# Caravan_Tracker.net
KiCad netlist of a schematic drawn in EAGLE
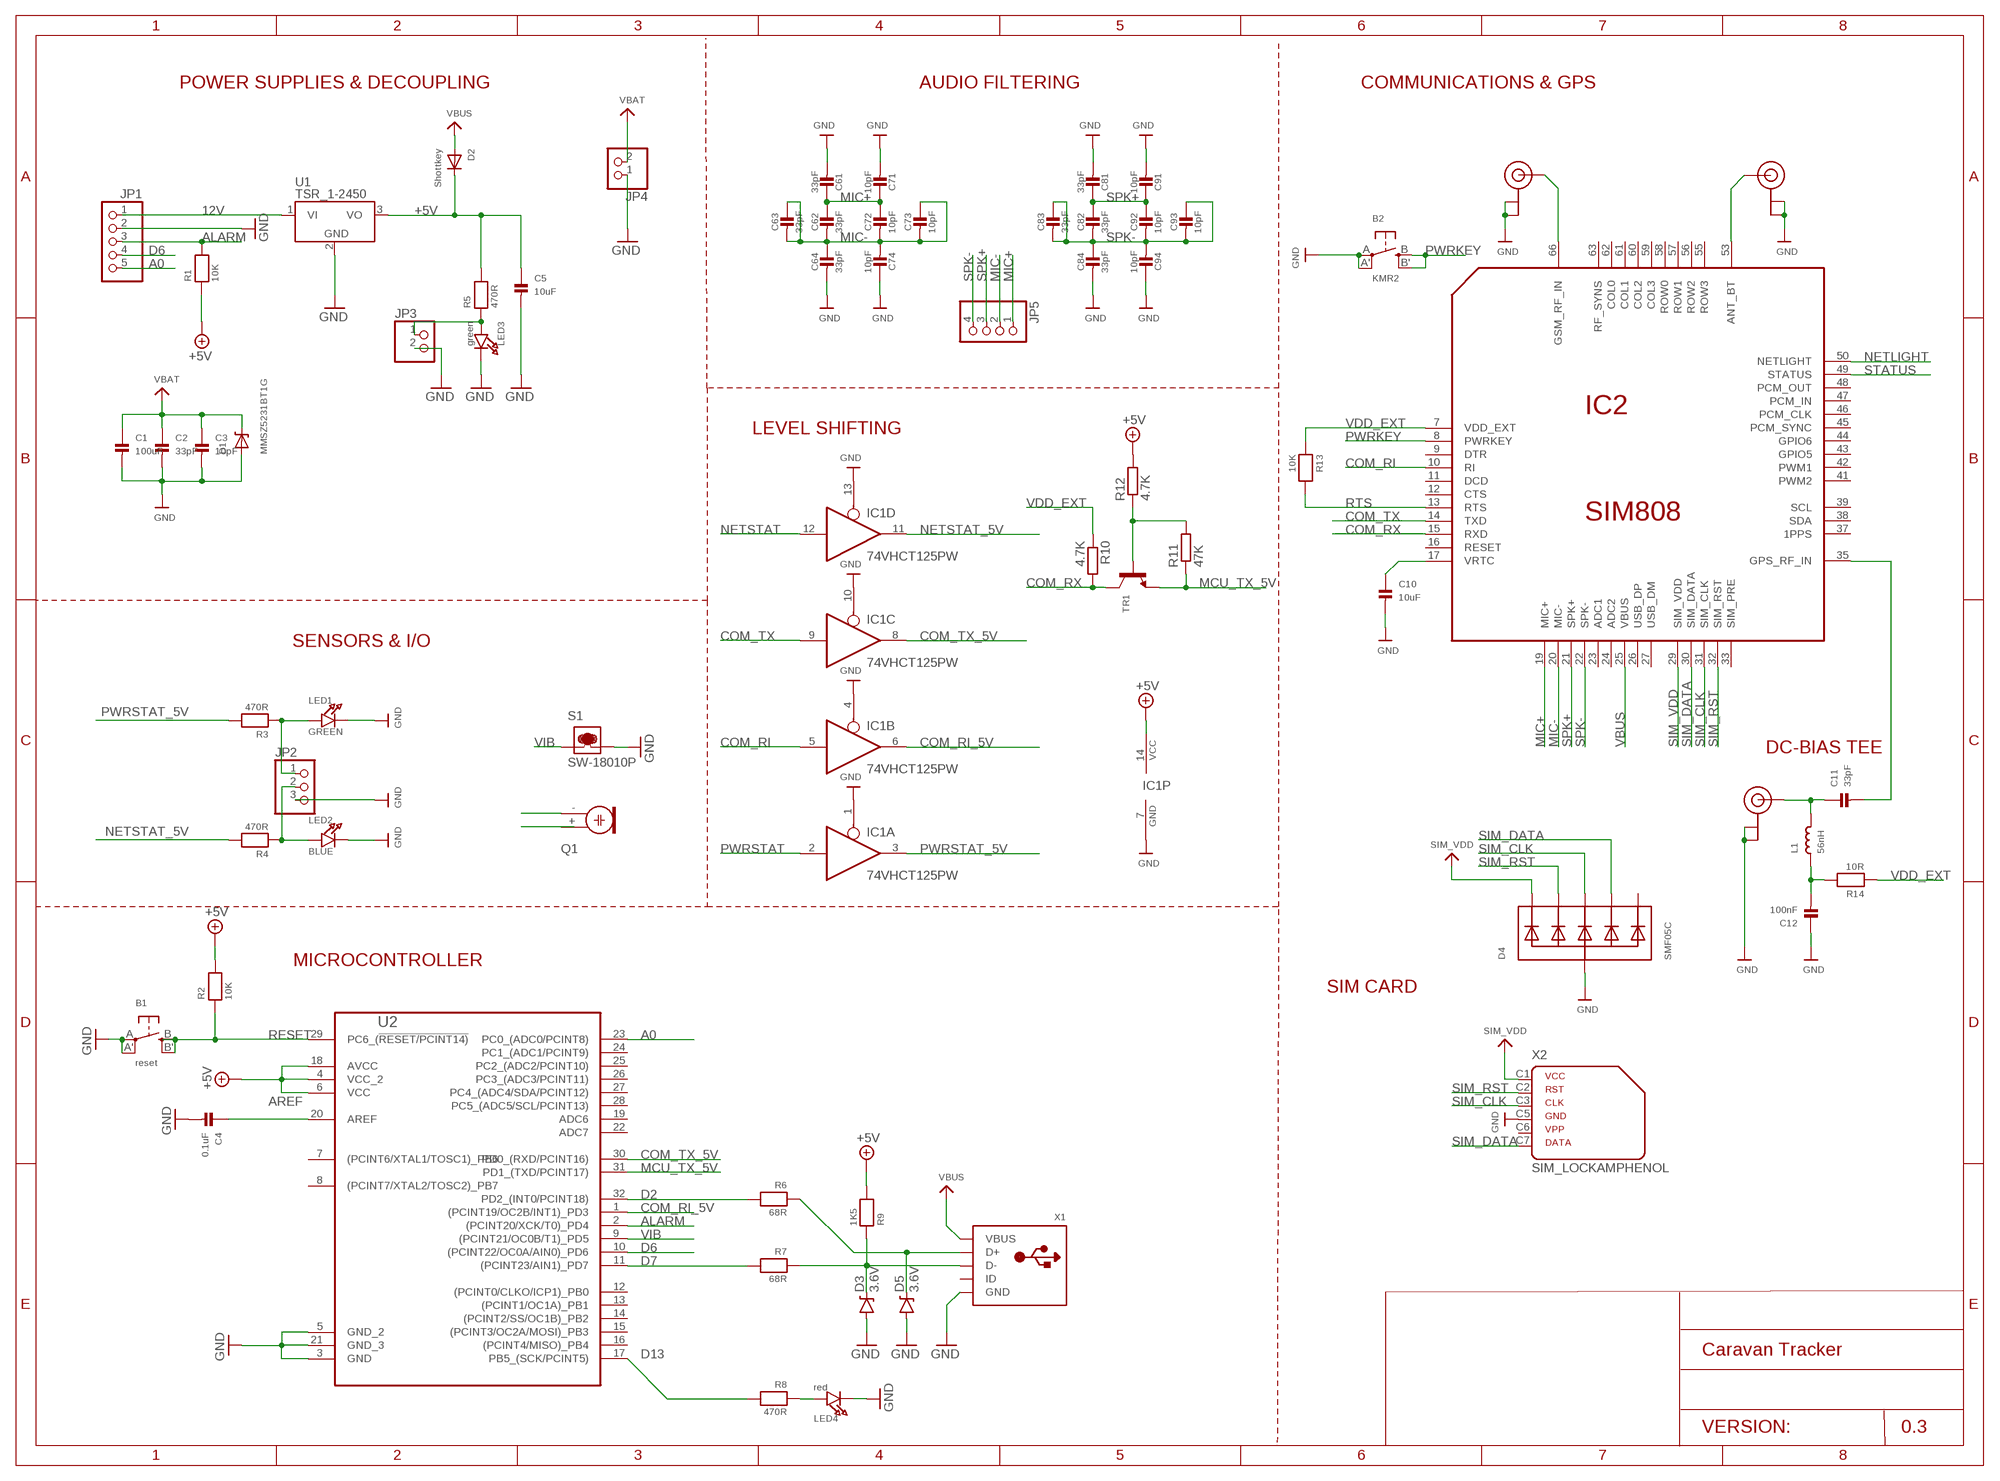
[diagram p0: schematic, sheet 1]

(export (version "E")
  (design (tool "Eeschema 10.0.6"))
  (components
    (comp (ref "B1")
      (value "reset")
      (footprint "eagle-import:BTN_KMR2_4.6X2.8")
      (libsource (lib "eagle-import") (part "SWITCH_TACT_SMT4.6X2.8"))
    )
    (comp (ref "B2")
      (value "KMR2")
      (footprint "eagle-import:BTN_KMR2_4.6X2.8")
      (libsource (lib "eagle-import") (part "SWITCH_TACT_SMT4.6X2.8"))
    )
    (comp (ref "C1")
      (value "100uF")
      (footprint "eagle-import:1206")
      (libsource (lib "eagle-import") (part "CAP_CERAMIC1206"))
    )
    (comp (ref "C2")
      (value "33pF")
      (footprint "eagle-import:0805")
      (libsource (lib "eagle-import") (part "CAP_CERAMIC0805"))
    )
    (comp (ref "C3")
      (value "10pF")
      (footprint "eagle-import:0805")
      (libsource (lib "eagle-import") (part "CAP_CERAMIC0805"))
    )
    (comp (ref "C4")
      (value "0.1uF")
      (footprint "eagle-import:0603")
      (libsource (lib "eagle-import") (part "CAP_CERAMIC0603"))
    )
    (comp (ref "C5")
      (value "10uF")
      (footprint "eagle-import:0603")
      (libsource (lib "eagle-import") (part "CAP_CERAMIC0603"))
    )
    (comp (ref "C6")
      (value "33pF")
      (footprint "eagle-import:RESPACK_4X0603")
      (libsource (lib "eagle-import") (part "CAP_4PACK1206"))
    )
    (comp (ref "C7")
      (value "10pF")
      (footprint "eagle-import:RESPACK_4X0603")
      (libsource (lib "eagle-import") (part "CAP_4PACK1206"))
    )
    (comp (ref "C8")
      (value "33pF")
      (footprint "eagle-import:RESPACK_4X0603")
      (libsource (lib "eagle-import") (part "CAP_4PACK1206"))
    )
    (comp (ref "C9")
      (value "10pF")
      (footprint "eagle-import:RESPACK_4X0603")
      (libsource (lib "eagle-import") (part "CAP_4PACK1206"))
    )
    (comp (ref "C10")
      (value "10uF")
      (footprint "eagle-import:0805")
      (libsource (lib "eagle-import") (part "CAP_CERAMIC0805"))
    )
    (comp (ref "C11")
      (value "33pF")
      (footprint "eagle-import:0805")
      (libsource (lib "eagle-import") (part "CAP_CERAMIC0805"))
    )
    (comp (ref "C12")
      (value "100nF")
      (footprint "eagle-import:0805")
      (libsource (lib "eagle-import") (part "CAP_CERAMIC0805"))
    )
    (comp (ref "D1")
      (value "MMSZ5231BT1G")
      (footprint "eagle-import:SOD-123")
      (libsource (lib "eagle-import") (part "DIODE-ZENERSOD123"))
    )
    (comp (ref "D2")
      (value "Shottkey")
      (footprint "eagle-import:SOD-123")
      (libsource (lib "eagle-import") (part "DIODESOD-123"))
    )
    (comp (ref "D3")
      (value "3.6V")
      (footprint "eagle-import:SOD-323")
      (libsource (lib "eagle-import") (part "DIODE-ZENER3.3V"))
    )
    (comp (ref "D4")
      (value "SMF05C")
      (footprint "eagle-import:SOT363")
      (libsource (lib "eagle-import") (part "TVSARRAY_5LANE"))
    )
    (comp (ref "D5")
      (value "3.6V")
      (footprint "eagle-import:SOD-323")
      (libsource (lib "eagle-import") (part "DIODE-ZENER3.3V"))
    )
    (comp (ref "IC1")
      (value "74VHCT125PW")
      (footprint "eagle-import:TSSOP14")
      (libsource (lib "eagle-import") (part "74125PWABT"))
    )
    (comp (ref "IC2")
      (value "SIM808")
      (footprint "eagle-import:SIM808")
      (libsource (lib "eagle-import") (part "SIM808"))
    )
    (comp (ref "JP1")
      (value "HEADER-1X5ROUND")
      (footprint "eagle-import:1X05_ROUND")
      (libsource (lib "eagle-import") (part "HEADER-1X5ROUND"))
    )
    (comp (ref "JP2")
      (value "HEADER-1X3ROUND")
      (footprint "eagle-import:1X03_ROUND")
      (libsource (lib "eagle-import") (part "HEADER-1X3ROUND"))
    )
    (comp (ref "JP3")
      (value "HEADER-1X2ROUND")
      (footprint "eagle-import:1X02_ROUND")
      (libsource (lib "eagle-import") (part "HEADER-1X2ROUND"))
    )
    (comp (ref "JP4")
      (value "JST_2PIN")
      (footprint "eagle-import:JSTPH2")
      (libsource (lib "eagle-import") (part "JST_2PIN"))
    )
    (comp (ref "JP5")
      (value "HEADER-1X4ROUND")
      (footprint "eagle-import:1X04_ROUND")
      (libsource (lib "eagle-import") (part "HEADER-1X4ROUND"))
    )
    (comp (ref "L1")
      (value "56nH")
      (footprint "eagle-import:_0805")
      (libsource (lib "eagle-import") (part "INDUCTOR_0805"))
    )
    (comp (ref "LED1")
      (value "GREEN")
      (footprint "eagle-import:CHIPLED_0805_NOOUTLINE")
      (libsource (lib "eagle-import") (part "LED0805_NOOUTLINE"))
    )
    (comp (ref "LED2")
      (value "BLUE")
      (footprint "eagle-import:CHIPLED_0805_NOOUTLINE")
      (libsource (lib "eagle-import") (part "LED0805_NOOUTLINE"))
    )
    (comp (ref "LED3")
      (value "green")
      (footprint "eagle-import:CHIPLED_0805_NOOUTLINE")
      (libsource (lib "eagle-import") (part "LED0805_NOOUTLINE"))
    )
    (comp (ref "LED4")
      (value "red")
      (footprint "eagle-import:CHIPLED_0805_NOOUTLINE")
      (libsource (lib "eagle-import") (part "LED0805_NOOUTLINE"))
    )
    (comp (ref "Q1")
      (value "ELECTRET")
      (footprint "eagle-import:9.7ELECTRET")
      (libsource (lib "eagle-import") (part "ELECTRET"))
    )
    (comp (ref "R1")
      (value "10K")
      (footprint "eagle-import:0603")
      (libsource (lib "eagle-import") (part "RESISTOR0603"))
    )
    (comp (ref "R2")
      (value "10K")
      (footprint "eagle-import:0603")
      (libsource (lib "eagle-import") (part "RESISTOR0603"))
    )
    (comp (ref "R3")
      (value "470R")
      (footprint "eagle-import:0603")
      (libsource (lib "eagle-import") (part "RESISTOR0603"))
    )
    (comp (ref "R4")
      (value "470R")
      (footprint "eagle-import:0603")
      (libsource (lib "eagle-import") (part "RESISTOR0603"))
    )
    (comp (ref "R5")
      (value "470R")
      (footprint "eagle-import:0603")
      (libsource (lib "eagle-import") (part "RESISTOR0603"))
    )
    (comp (ref "R6")
      (value "68R")
      (footprint "eagle-import:0603")
      (libsource (lib "eagle-import") (part "RESISTOR0603"))
    )
    (comp (ref "R7")
      (value "68R")
      (footprint "eagle-import:0603")
      (libsource (lib "eagle-import") (part "RESISTOR0603"))
    )
    (comp (ref "R8")
      (value "470R")
      (footprint "eagle-import:0603")
      (libsource (lib "eagle-import") (part "RESISTOR0603"))
    )
    (comp (ref "R9")
      (value "1K5")
      (footprint "eagle-import:0603")
      (libsource (lib "eagle-import") (part "RESISTOR0603"))
    )
    (comp (ref "R10")
      (value "4.7K")
      (footprint "eagle-import:R0603")
      (libsource (lib "eagle-import") (part "R-EU_R0603"))
    )
    (comp (ref "R11")
      (value "47K")
      (footprint "eagle-import:R0603")
      (libsource (lib "eagle-import") (part "R-EU_R0603"))
    )
    (comp (ref "R12")
      (value "4.7K")
      (footprint "eagle-import:R0603")
      (libsource (lib "eagle-import") (part "R-EU_R0603"))
    )
    (comp (ref "R13")
      (value "10K")
      (footprint "eagle-import:0603")
      (libsource (lib "eagle-import") (part "RESISTOR0603"))
    )
    (comp (ref "R14")
      (value "10R")
      (footprint "eagle-import:_0805")
      (libsource (lib "eagle-import") (part "RESISTOR_0805"))
    )
    (comp (ref "S1")
      (value "SW-18010P")
      (footprint "eagle-import:SW-18010P")
      (libsource (lib "eagle-import") (part "SW-18010P"))
    )
    (comp (ref "TR1")
      (value "TRANSISTOR_NPN")
      (footprint "eagle-import:SOT23-R")
      (libsource (lib "eagle-import") (part "TRANSISTOR_NPN"))
    )
    (comp (ref "U$1")
      (value "U.FL (GPS)")
      (footprint "eagle-import:U.FL")
      (libsource (lib "eagle-import") (part "U.FL"))
    )
    (comp (ref "U$2")
      (value "U.FL")
      (footprint "eagle-import:U.FL")
      (libsource (lib "eagle-import") (part "U.FL"))
    )
    (comp (ref "U$3")
      (value "U.FL")
      (footprint "eagle-import:U.FL")
      (libsource (lib "eagle-import") (part "U.FL"))
    )
    (comp (ref "U1")
      (value "TSR_1-2450")
      (footprint "eagle-import:TSR-1")
      (libsource (lib "eagle-import") (part "TSR_1-2450"))
    )
    (comp (ref "U2")
      (value "ATMEGA328-AU")
      (footprint "eagle-import:QFP80P900X900X120-32N")
      (libsource (lib "eagle-import") (part "ATMEGA328-AU"))
    )
    (comp (ref "X1")
      (value "USBMICRO_20329")
      (footprint "eagle-import:4UCONN_20329")
      (libsource (lib "eagle-import") (part "USBMICRO_20329"))
    )
    (comp (ref "X2")
      (value "SIM_LOCKAMPHENOL")
      (footprint "eagle-import:C707_10M006_512_2")
      (libsource (lib "eagle-import") (part "SIM_LOCKAMPHENOL"))
    )
  )
  (nets
    (net (code "1") (name "+5V") (class "Default")
      (node (ref "C5") (pin "1") (pinfunction "P$1_1") (pintype "passive"))
      (node (ref "D2") (pin "C") (pinfunction "C_C") (pintype "passive"))
      (node (ref "IC1") (pin "14") (pinfunction "VCC_14") (pintype "power_in"))
      (node (ref "R1") (pin "1") (pinfunction "1_1") (pintype "passive"))
      (node (ref "R12") (pin "2") (pinfunction "2_2") (pintype "passive"))
      (node (ref "R2") (pin "2") (pinfunction "2_2") (pintype "passive"))
      (node (ref "R5") (pin "2") (pinfunction "2_2") (pintype "passive"))
      (node (ref "R9") (pin "2") (pinfunction "2_2") (pintype "passive"))
      (node (ref "U1") (pin "3") (pinfunction "VO_3") (pintype "power_in"))
      (node (ref "U2") (pin "18") (pinfunction "AVCC_18") (pintype "power_in"))
      (node (ref "U2") (pin "4") (pinfunction "VCC_2_4") (pintype "power_in"))
      (node (ref "U2") (pin "6") (pinfunction "VCC_6") (pintype "power_in"))
    )
    (net (code "2") (name "/12V") (class "Default")
      (node (ref "JP1") (pin "1") (pinfunction "1_1") (pintype "passive"))
      (node (ref "U1") (pin "1") (pinfunction "VI_1") (pintype "power_in"))
    )
    (net (code "3") (name "/A0") (class "Default")
      (node (ref "JP1") (pin "5") (pinfunction "5_5") (pintype "passive"))
      (node (ref "U2") (pin "23") (pinfunction "PC0_(ADC0/PCINT8)_23") (pintype "bidirectional"))
    )
    (net (code "4") (name "/ALARM") (class "Default")
      (node (ref "JP1") (pin "3") (pinfunction "3_3") (pintype "passive"))
      (node (ref "R1") (pin "2") (pinfunction "2_2") (pintype "passive"))
      (node (ref "U2") (pin "2") (pinfunction "(PCINT20/XCK/T0)_PD4_2") (pintype "bidirectional"))
    )
    (net (code "5") (name "/AREF") (class "Default")
      (node (ref "C4") (pin "1") (pinfunction "P$1_1") (pintype "passive"))
      (node (ref "U2") (pin "20") (pinfunction "AREF_20") (pintype "passive"))
    )
    (net (code "6") (name "/COM_RI") (class "Default")
      (node (ref "IC1") (pin "5") (pinfunction "I_5") (pintype "input"))
      (node (ref "IC2") (pin "10") (pinfunction "RI_10") (pintype "bidirectional"))
    )
    (net (code "7") (name "/COM_RI_5V") (class "Default")
      (node (ref "IC1") (pin "6") (pinfunction "O_6") (pintype "tri_state"))
      (node (ref "U2") (pin "1") (pinfunction "(PCINT19/OC2B/INT1)_PD3_1") (pintype "bidirectional"))
    )
    (net (code "8") (name "/COM_RX") (class "Default")
      (node (ref "IC2") (pin "15") (pinfunction "RXD_15") (pintype "bidirectional"))
      (node (ref "R10") (pin "2") (pinfunction "2_2") (pintype "passive"))
      (node (ref "TR1") (pin "3") (pinfunction "C_3") (pintype "passive"))
    )
    (net (code "9") (name "/COM_TX") (class "Default")
      (node (ref "IC1") (pin "9") (pinfunction "I_9") (pintype "input"))
      (node (ref "IC2") (pin "14") (pinfunction "TXD_14") (pintype "bidirectional"))
    )
    (net (code "10") (name "/COM_TX_5V") (class "Default")
      (node (ref "IC1") (pin "8") (pinfunction "O_8") (pintype "tri_state"))
      (node (ref "U2") (pin "30") (pinfunction "PD0_(RXD/PCINT16)_30") (pintype "bidirectional"))
    )
    (net (code "11") (name "/D2") (class "Default")
      (node (ref "R6") (pin "2") (pinfunction "2_2") (pintype "passive"))
      (node (ref "U2") (pin "32") (pinfunction "PD2_(INT0/PCINT18)_32") (pintype "bidirectional"))
    )
    (net (code "12") (name "/D6") (class "Default")
      (node (ref "JP1") (pin "4") (pinfunction "4_4") (pintype "passive"))
      (node (ref "U2") (pin "10") (pinfunction "(PCINT22/OC0A/AIN0)_PD6_10") (pintype "bidirectional"))
    )
    (net (code "13") (name "/D7") (class "Default")
      (node (ref "R7") (pin "2") (pinfunction "2_2") (pintype "passive"))
      (node (ref "U2") (pin "11") (pinfunction "(PCINT23/AIN1)_PD7_11") (pintype "bidirectional"))
    )
    (net (code "14") (name "/D13") (class "Default")
      (node (ref "R8") (pin "2") (pinfunction "2_2") (pintype "passive"))
      (node (ref "U2") (pin "17") (pinfunction "PB5_(SCK/PCINT5)_17") (pintype "bidirectional"))
    )
    (net (code "15") (name "/MCU_TX_5V") (class "Default")
      (node (ref "R11") (pin "1") (pinfunction "1_1") (pintype "passive"))
      (node (ref "TR1") (pin "2") (pinfunction "E_2") (pintype "passive"))
      (node (ref "U2") (pin "31") (pinfunction "PD1_(TXD/PCINT17)_31") (pintype "bidirectional"))
    )
    (net (code "16") (name "/MIC+") (class "Default")
      (node (ref "C6") (pin "1") (pinfunction "1_1") (pintype "passive"))
      (node (ref "C6") (pin "2") (pinfunction "1_2") (pintype "passive"))
      (node (ref "C7") (pin "1") (pinfunction "1_1") (pintype "passive"))
      (node (ref "C7") (pin "2") (pinfunction "1_2") (pintype "passive"))
      (node (ref "IC2") (pin "19") (pinfunction "MIC+_19") (pintype "bidirectional"))
      (node (ref "JP5") (pin "1") (pinfunction "1_1") (pintype "passive"))
    )
    (net (code "17") (name "/MIC-") (class "Default")
      (node (ref "C6") (pin "3") (pinfunction "1_3") (pintype "passive"))
      (node (ref "C6") (pin "4") (pinfunction "1_4") (pintype "passive"))
      (node (ref "C6") (pin "6") (pinfunction "2_6") (pintype "passive"))
      (node (ref "C6") (pin "7") (pinfunction "2_7") (pintype "passive"))
      (node (ref "C7") (pin "3") (pinfunction "1_3") (pintype "passive"))
      (node (ref "C7") (pin "5") (pinfunction "2_5") (pintype "passive"))
      (node (ref "C7") (pin "6") (pinfunction "2_6") (pintype "passive"))
      (node (ref "C7") (pin "7") (pinfunction "2_7") (pintype "passive"))
      (node (ref "IC2") (pin "20") (pinfunction "MIC-_20") (pintype "bidirectional"))
      (node (ref "JP5") (pin "2") (pinfunction "2_2") (pintype "passive"))
      (node (ref "Q1") (pin "-") (pinfunction "1_-") (pintype "passive"))
    )
    (net (code "18") (name "/NETLIGHT") (class "Default")
      (node (ref "IC2") (pin "50") (pinfunction "NETLIGHT_50") (pintype "bidirectional"))
    )
    (net (code "19") (name "/NETSTAT") (class "Default")
      (node (ref "IC1") (pin "12") (pinfunction "I_12") (pintype "input"))
    )
    (net (code "20") (name "/NETSTAT_5V") (class "Default")
      (node (ref "IC1") (pin "11") (pinfunction "O_11") (pintype "tri_state"))
      (node (ref "R4") (pin "2") (pinfunction "2_2") (pintype "passive"))
    )
    (net (code "21") (name "/PWRKEY") (class "Default")
      (node (ref "B2") (pin "B") (pinfunction "S_B") (pintype "passive"))
      (node (ref "B2") (pin "B'") (pinfunction "S1_B'") (pintype "passive"))
      (node (ref "IC2") (pin "8") (pinfunction "PWRKEY_8") (pintype "bidirectional"))
    )
    (net (code "22") (name "/PWRSTAT") (class "Default")
      (node (ref "IC1") (pin "2") (pinfunction "I_2") (pintype "input"))
    )
    (net (code "23") (name "/PWRSTAT_5V") (class "Default")
      (node (ref "IC1") (pin "3") (pinfunction "O_3") (pintype "tri_state"))
      (node (ref "R3") (pin "2") (pinfunction "2_2") (pintype "passive"))
    )
    (net (code "24") (name "/RESET") (class "Default")
      (node (ref "B1") (pin "B") (pinfunction "S_B") (pintype "passive"))
      (node (ref "B1") (pin "B'") (pinfunction "S1_B'") (pintype "passive"))
      (node (ref "R2") (pin "1") (pinfunction "1_1") (pintype "passive"))
      (node (ref "U2") (pin "29") (pinfunction "PC6_(~{RESET/PCINT14})_29") (pintype "bidirectional"))
    )
    (net (code "25") (name "/RTS") (class "Default")
      (node (ref "IC2") (pin "13") (pinfunction "RTS_13") (pintype "bidirectional"))
      (node (ref "R13") (pin "2") (pinfunction "2_2") (pintype "passive"))
    )
    (net (code "26") (name "/SIM_CLK") (class "Default")
      (node (ref "D4") (pin "4") (pinfunction "C3_4") (pintype "passive"))
      (node (ref "IC2") (pin "31") (pinfunction "SIM_CLK_31") (pintype "bidirectional"))
      (node (ref "X2") (pin "C3") (pinfunction "3_C3") (pintype "passive"))
    )
    (net (code "27") (name "/SIM_DATA") (class "Default")
      (node (ref "D4") (pin "5") (pinfunction "C4_5") (pintype "passive"))
      (node (ref "IC2") (pin "30") (pinfunction "SIM_DATA_30") (pintype "bidirectional"))
      (node (ref "X2") (pin "C7") (pinfunction "6_C7") (pintype "passive"))
    )
    (net (code "28") (name "/SIM_RST") (class "Default")
      (node (ref "D4") (pin "3") (pinfunction "C2_3") (pintype "passive"))
      (node (ref "IC2") (pin "32") (pinfunction "SIM_RST_32") (pintype "bidirectional"))
      (node (ref "X2") (pin "C2") (pinfunction "2_C2") (pintype "passive"))
    )
    (net (code "29") (name "/SPK+") (class "Default")
      (node (ref "C8") (pin "1") (pinfunction "1_1") (pintype "passive"))
      (node (ref "C8") (pin "2") (pinfunction "1_2") (pintype "passive"))
      (node (ref "C9") (pin "1") (pinfunction "1_1") (pintype "passive"))
      (node (ref "C9") (pin "2") (pinfunction "1_2") (pintype "passive"))
      (node (ref "IC2") (pin "21") (pinfunction "SPK+_21") (pintype "bidirectional"))
      (node (ref "JP5") (pin "3") (pinfunction "3_3") (pintype "passive"))
    )
    (net (code "30") (name "/SPK-") (class "Default")
      (node (ref "C8") (pin "3") (pinfunction "1_3") (pintype "passive"))
      (node (ref "C8") (pin "4") (pinfunction "1_4") (pintype "passive"))
      (node (ref "C8") (pin "6") (pinfunction "2_6") (pintype "passive"))
      (node (ref "C8") (pin "7") (pinfunction "2_7") (pintype "passive"))
      (node (ref "C9") (pin "3") (pinfunction "1_3") (pintype "passive"))
      (node (ref "C9") (pin "5") (pinfunction "2_5") (pintype "passive"))
      (node (ref "C9") (pin "6") (pinfunction "2_6") (pintype "passive"))
      (node (ref "C9") (pin "7") (pinfunction "2_7") (pintype "passive"))
      (node (ref "IC2") (pin "22") (pinfunction "SPK-_22") (pintype "bidirectional"))
      (node (ref "JP5") (pin "4") (pinfunction "4_4") (pintype "passive"))
    )
    (net (code "31") (name "/STATUS") (class "Default")
      (node (ref "IC2") (pin "49") (pinfunction "STATUS_49") (pintype "bidirectional"))
    )
    (net (code "32") (name "/VDD_EXT") (class "Default")
      (node (ref "IC2") (pin "7") (pinfunction "VDD_EXT_7") (pintype "bidirectional"))
      (node (ref "R10") (pin "1") (pinfunction "1_1") (pintype "passive"))
      (node (ref "R13") (pin "1") (pinfunction "1_1") (pintype "passive"))
      (node (ref "R14") (pin "1") (pinfunction "1_1") (pintype "passive"))
    )
    (net (code "33") (name "/VIB") (class "Default")
      (node (ref "S1") (pin "2") (pinfunction "2_2") (pintype "passive"))
      (node (ref "U2") (pin "9") (pinfunction "(PCINT21/OC0B/T1)_PD5_9") (pintype "bidirectional"))
    )
    (net (code "34") (name "GND") (class "Default")
      (node (ref "B1") (pin "A") (pinfunction "P_A") (pintype "passive"))
      (node (ref "B1") (pin "A'") (pinfunction "P1_A'") (pintype "passive"))
      (node (ref "B2") (pin "A") (pinfunction "P_A") (pintype "passive"))
      (node (ref "B2") (pin "A'") (pinfunction "P1_A'") (pintype "passive"))
      (node (ref "C1") (pin "2") (pinfunction "P$2_2") (pintype "passive"))
      (node (ref "C10") (pin "2") (pinfunction "P$2_2") (pintype "passive"))
      (node (ref "C12") (pin "1") (pinfunction "P$1_1") (pintype "passive"))
      (node (ref "C2") (pin "2") (pinfunction "P$2_2") (pintype "passive"))
      (node (ref "C3") (pin "2") (pinfunction "P$2_2") (pintype "passive"))
      (node (ref "C4") (pin "2") (pinfunction "P$2_2") (pintype "passive"))
      (node (ref "C5") (pin "2") (pinfunction "P$2_2") (pintype "passive"))
      (node (ref "C6") (pin "5") (pinfunction "2_5") (pintype "passive"))
      (node (ref "C6") (pin "8") (pinfunction "2_8") (pintype "passive"))
      (node (ref "C7") (pin "4") (pinfunction "1_4") (pintype "passive"))
      (node (ref "C7") (pin "8") (pinfunction "2_8") (pintype "passive"))
      (node (ref "C8") (pin "5") (pinfunction "2_5") (pintype "passive"))
      (node (ref "C8") (pin "8") (pinfunction "2_8") (pintype "passive"))
      (node (ref "C9") (pin "4") (pinfunction "1_4") (pintype "passive"))
      (node (ref "C9") (pin "8") (pinfunction "2_8") (pintype "passive"))
      (node (ref "D1") (pin "A") (pinfunction "A_A") (pintype "passive"))
      (node (ref "D3") (pin "A") (pinfunction "A_A") (pintype "passive"))
      (node (ref "D4") (pin "2") (pinfunction "A_2") (pintype "passive"))
      (node (ref "D5") (pin "A") (pinfunction "A_A") (pintype "passive"))
      (node (ref "IC1") (pin "1") (pinfunction "OE_1") (pintype "input"))
      (node (ref "IC1") (pin "10") (pinfunction "OE_10") (pintype "input"))
      (node (ref "IC1") (pin "13") (pinfunction "OE_13") (pintype "input"))
      (node (ref "IC1") (pin "4") (pinfunction "OE_4") (pintype "input"))
      (node (ref "IC1") (pin "7") (pinfunction "GND_7") (pintype "power_in"))
      (node (ref "JP1") (pin "2") (pinfunction "2_2") (pintype "passive"))
      (node (ref "JP2") (pin "3") (pinfunction "3_3") (pintype "passive"))
      (node (ref "JP3") (pin "2") (pinfunction "2_2") (pintype "passive"))
      (node (ref "JP4") (pin "1") (pinfunction "1_1") (pintype "passive"))
      (node (ref "LED1") (pin "C") (pinfunction "C_C") (pintype "passive"))
      (node (ref "LED2") (pin "C") (pinfunction "C_C") (pintype "passive"))
      (node (ref "LED3") (pin "C") (pinfunction "C_C") (pintype "passive"))
      (node (ref "LED4") (pin "C") (pinfunction "C_C") (pintype "passive"))
      (node (ref "S1") (pin "1") (pinfunction "1_1") (pintype "passive"))
      (node (ref "U$1") (pin "1") (pinfunction "GND_1") (pintype "passive"))
      (node (ref "U$1") (pin "2") (pinfunction "GND_2") (pintype "passive"))
      (node (ref "U$2") (pin "1") (pinfunction "GND_1") (pintype "passive"))
      (node (ref "U$2") (pin "2") (pinfunction "GND_2") (pintype "passive"))
      (node (ref "U$3") (pin "1") (pinfunction "GND_1") (pintype "passive"))
      (node (ref "U$3") (pin "2") (pinfunction "GND_2") (pintype "passive"))
      (node (ref "U1") (pin "2") (pinfunction "GND_2") (pintype "power_in"))
      (node (ref "U2") (pin "21") (pinfunction "GND_3_21") (pintype "passive"))
      (node (ref "U2") (pin "3") (pinfunction "GND_3") (pintype "passive"))
      (node (ref "U2") (pin "5") (pinfunction "GND_2_5") (pintype "passive"))
      (node (ref "X1") (pin "BASE@1") (pinfunction "GND_BASE@1") (pintype "power_in"))
      (node (ref "X1") (pin "BASE@2") (pinfunction "GND_BASE@2") (pintype "power_in"))
      (node (ref "X1") (pin "GND") (pinfunction "GND_GND") (pintype "power_in"))
      (node (ref "X1") (pin "SPRT@1") (pinfunction "GND_SPRT@1") (pintype "power_in"))
      (node (ref "X1") (pin "SPRT@2") (pinfunction "GND_SPRT@2") (pintype "power_in"))
      (node (ref "X1") (pin "SPRT@3") (pinfunction "GND_SPRT@3") (pintype "power_in"))
      (node (ref "X1") (pin "SPRT@4") (pinfunction "GND_SPRT@4") (pintype "power_in"))
      (node (ref "X2") (pin "C5") (pinfunction "4_C5") (pintype "passive"))
    )
    (net (code "35") (name "Net-(C10-P$1)") (class "Default")
      (node (ref "C10") (pin "1") (pinfunction "P$1_1") (pintype "passive"))
      (node (ref "IC2") (pin "17") (pinfunction "VRTC_17") (pintype "bidirectional"))
    )
    (net (code "36") (name "Net-(C11-P$1)") (class "Default")
      (node (ref "C11") (pin "1") (pinfunction "P$1_1") (pintype "passive"))
      (node (ref "L1") (pin "2") (pinfunction "2_2") (pintype "passive"))
      (node (ref "U$1") (pin "3") (pinfunction "SIGNAL_3") (pintype "passive"))
    )
    (net (code "37") (name "Net-(C11-P$2)") (class "Default")
      (node (ref "C11") (pin "2") (pinfunction "P$2_2") (pintype "passive"))
      (node (ref "IC2") (pin "35") (pinfunction "GPS_RF_IN_35") (pintype "bidirectional"))
    )
    (net (code "38") (name "Net-(C12-P$2)") (class "Default")
      (node (ref "C12") (pin "2") (pinfunction "P$2_2") (pintype "passive"))
      (node (ref "L1") (pin "1") (pinfunction "1_1") (pintype "passive"))
      (node (ref "R14") (pin "2") (pinfunction "2_2") (pintype "passive"))
    )
    (net (code "39") (name "Net-(D3-PadC)") (class "Default")
      (node (ref "D3") (pin "C") (pinfunction "C_C") (pintype "passive"))
      (node (ref "R7") (pin "1") (pinfunction "1_1") (pintype "passive"))
      (node (ref "R9") (pin "1") (pinfunction "1_1") (pintype "passive"))
      (node (ref "X1") (pin "D-") (pinfunction "D-_D-") (pintype "bidirectional"))
    )
    (net (code "40") (name "Net-(D5-PadC)") (class "Default")
      (node (ref "D5") (pin "C") (pinfunction "C_C") (pintype "passive"))
      (node (ref "R6") (pin "1") (pinfunction "1_1") (pintype "passive"))
      (node (ref "X1") (pin "D+") (pinfunction "D+_D+") (pintype "bidirectional"))
    )
    (net (code "41") (name "Net-(IC2A-ANT_BT)") (class "Default")
      (node (ref "IC2") (pin "53") (pinfunction "ANT_BT_53") (pintype "bidirectional"))
      (node (ref "U$3") (pin "3") (pinfunction "SIGNAL_3") (pintype "passive"))
    )
    (net (code "42") (name "Net-(IC2A-GSM_RF_IN)") (class "Default")
      (node (ref "IC2") (pin "66") (pinfunction "GSM_RF_IN_66") (pintype "bidirectional"))
      (node (ref "U$2") (pin "3") (pinfunction "SIGNAL_3") (pintype "passive"))
    )
    (net (code "43") (name "Net-(JP2-Pad1)") (class "Default")
      (node (ref "JP2") (pin "1") (pinfunction "1_1") (pintype "passive"))
      (node (ref "LED1") (pin "A") (pinfunction "A_A") (pintype "passive"))
      (node (ref "R3") (pin "1") (pinfunction "1_1") (pintype "passive"))
    )
    (net (code "44") (name "Net-(JP2-Pad2)") (class "Default")
      (node (ref "JP2") (pin "2") (pinfunction "2_2") (pintype "passive"))
      (node (ref "LED2") (pin "A") (pinfunction "A_A") (pintype "passive"))
      (node (ref "R4") (pin "1") (pinfunction "1_1") (pintype "passive"))
    )
    (net (code "45") (name "Net-(JP3-Pad1)") (class "Default")
      (node (ref "JP3") (pin "1") (pinfunction "1_1") (pintype "passive"))
      (node (ref "LED3") (pin "A") (pinfunction "A_A") (pintype "passive"))
      (node (ref "R5") (pin "1") (pinfunction "1_1") (pintype "passive"))
    )
    (net (code "46") (name "Net-(LED4-PadA)") (class "Default")
      (node (ref "LED4") (pin "A") (pinfunction "A_A") (pintype "passive"))
      (node (ref "R8") (pin "1") (pinfunction "1_1") (pintype "passive"))
    )
    (net (code "47") (name "Net-(TR1-B)") (class "Default")
      (node (ref "R11") (pin "2") (pinfunction "2_2") (pintype "passive"))
      (node (ref "R12") (pin "1") (pinfunction "1_1") (pintype "passive"))
      (node (ref "TR1") (pin "1") (pinfunction "B_1") (pintype "passive"))
    )
    (net (code "48") (name "SIM_VDD") (class "Default")
      (node (ref "D4") (pin "1") (pinfunction "C1_1") (pintype "passive"))
      (node (ref "IC2") (pin "29") (pinfunction "SIM_VDD_29") (pintype "bidirectional"))
      (node (ref "X2") (pin "C1") (pinfunction "1_C1") (pintype "passive"))
    )
    (net (code "49") (name "VBAT") (class "Default")
      (node (ref "C1") (pin "1") (pinfunction "P$1_1") (pintype "passive"))
      (node (ref "C2") (pin "1") (pinfunction "P$1_1") (pintype "passive"))
      (node (ref "C3") (pin "1") (pinfunction "P$1_1") (pintype "passive"))
      (node (ref "D1") (pin "C") (pinfunction "C_C") (pintype "passive"))
      (node (ref "JP4") (pin "2") (pinfunction "2_2") (pintype "passive"))
    )
    (net (code "50") (name "VBUS") (class "Default")
      (node (ref "D2") (pin "A") (pinfunction "A_A") (pintype "passive"))
      (node (ref "IC2") (pin "25") (pinfunction "VBUS_25") (pintype "bidirectional"))
      (node (ref "X1") (pin "VBUS") (pinfunction "VBUS_VBUS") (pintype "power_in"))
    )
    (net (code "51") (name "unconnected-(D4-C5-Pad6)") (class "Default")
      (node (ref "D4") (pin "6") (pinfunction "C5_6") (pintype "passive"))
    )
    (net (code "52") (name "unconnected-(IC2A-1PPS-Pad37)") (class "Default")
      (node (ref "IC2") (pin "37") (pinfunction "1PPS_37") (pintype "bidirectional"))
    )
    (net (code "53") (name "unconnected-(IC2A-ADC1-Pad23)") (class "Default")
      (node (ref "IC2") (pin "23") (pinfunction "ADC1_23") (pintype "bidirectional"))
    )
    (net (code "54") (name "unconnected-(IC2A-ADC2-Pad24)") (class "Default")
      (node (ref "IC2") (pin "24") (pinfunction "ADC2_24") (pintype "bidirectional"))
    )
    (net (code "55") (name "unconnected-(IC2A-COL0-Pad62)") (class "Default")
      (node (ref "IC2") (pin "62") (pinfunction "COL0_62") (pintype "bidirectional"))
    )
    (net (code "56") (name "unconnected-(IC2A-COL1-Pad61)") (class "Default")
      (node (ref "IC2") (pin "61") (pinfunction "COL1_61") (pintype "bidirectional"))
    )
    (net (code "57") (name "unconnected-(IC2A-COL2-Pad60)") (class "Default")
      (node (ref "IC2") (pin "60") (pinfunction "COL2_60") (pintype "bidirectional"))
    )
    (net (code "58") (name "unconnected-(IC2A-COL3-Pad59)") (class "Default")
      (node (ref "IC2") (pin "59") (pinfunction "COL3_59") (pintype "bidirectional"))
    )
    (net (code "59") (name "unconnected-(IC2A-CTS-Pad12)") (class "Default")
      (node (ref "IC2") (pin "12") (pinfunction "CTS_12") (pintype "bidirectional"))
    )
    (net (code "60") (name "unconnected-(IC2A-DCD-Pad11)") (class "Default")
      (node (ref "IC2") (pin "11") (pinfunction "DCD_11") (pintype "bidirectional"))
    )
    (net (code "61") (name "unconnected-(IC2A-DTR-Pad9)") (class "Default")
      (node (ref "IC2") (pin "9") (pinfunction "DTR_9") (pintype "bidirectional"))
    )
    (net (code "62") (name "unconnected-(IC2A-GPIO5-Pad43)") (class "Default")
      (node (ref "IC2") (pin "43") (pinfunction "GPIO5_43") (pintype "bidirectional"))
    )
    (net (code "63") (name "unconnected-(IC2A-GPIO6-Pad44)") (class "Default")
      (node (ref "IC2") (pin "44") (pinfunction "GPIO6_44") (pintype "bidirectional"))
    )
    (net (code "64") (name "unconnected-(IC2A-PCM_CLK-Pad46)") (class "Default")
      (node (ref "IC2") (pin "46") (pinfunction "PCM_CLK_46") (pintype "bidirectional"))
    )
    (net (code "65") (name "unconnected-(IC2A-PCM_IN-Pad47)") (class "Default")
      (node (ref "IC2") (pin "47") (pinfunction "PCM_IN_47") (pintype "bidirectional"))
    )
    (net (code "66") (name "unconnected-(IC2A-PCM_OUT-Pad48)") (class "Default")
      (node (ref "IC2") (pin "48") (pinfunction "PCM_OUT_48") (pintype "bidirectional"))
    )
    (net (code "67") (name "unconnected-(IC2A-PCM_SYNC-Pad45)") (class "Default")
      (node (ref "IC2") (pin "45") (pinfunction "PCM_SYNC_45") (pintype "bidirectional"))
    )
    (net (code "68") (name "unconnected-(IC2A-PWM1-Pad42)") (class "Default")
      (node (ref "IC2") (pin "42") (pinfunction "PWM1_42") (pintype "bidirectional"))
    )
    (net (code "69") (name "unconnected-(IC2A-PWM2-Pad41)") (class "Default")
      (node (ref "IC2") (pin "41") (pinfunction "PWM2_41") (pintype "bidirectional"))
    )
    (net (code "70") (name "unconnected-(IC2A-RESET-Pad16)") (class "Default")
      (node (ref "IC2") (pin "16") (pinfunction "RESET_16") (pintype "bidirectional"))
    )
    (net (code "71") (name "unconnected-(IC2A-RF_SYNS-Pad63)") (class "Default")
      (node (ref "IC2") (pin "63") (pinfunction "RF_SYNS_63") (pintype "bidirectional"))
    )
    (net (code "72") (name "unconnected-(IC2A-ROW0-Pad58)") (class "Default")
      (node (ref "IC2") (pin "58") (pinfunction "ROW0_58") (pintype "bidirectional"))
    )
    (net (code "73") (name "unconnected-(IC2A-ROW1-Pad57)") (class "Default")
      (node (ref "IC2") (pin "57") (pinfunction "ROW1_57") (pintype "bidirectional"))
    )
    (net (code "74") (name "unconnected-(IC2A-ROW2-Pad56)") (class "Default")
      (node (ref "IC2") (pin "56") (pinfunction "ROW2_56") (pintype "bidirectional"))
    )
    (net (code "75") (name "unconnected-(IC2A-ROW3-Pad55)") (class "Default")
      (node (ref "IC2") (pin "55") (pinfunction "ROW3_55") (pintype "bidirectional"))
    )
    (net (code "76") (name "unconnected-(IC2A-SCL-Pad39)") (class "Default")
      (node (ref "IC2") (pin "39") (pinfunction "SCL_39") (pintype "bidirectional"))
    )
    (net (code "77") (name "unconnected-(IC2A-SDA-Pad38)") (class "Default")
      (node (ref "IC2") (pin "38") (pinfunction "SDA_38") (pintype "bidirectional"))
    )
    (net (code "78") (name "unconnected-(IC2A-SIM_PRE-Pad33)") (class "Default")
      (node (ref "IC2") (pin "33") (pinfunction "SIM_PRE_33") (pintype "bidirectional"))
    )
    (net (code "79") (name "unconnected-(IC2A-USB_DM-Pad27)") (class "Default")
      (node (ref "IC2") (pin "27") (pinfunction "USB_DM_27") (pintype "bidirectional"))
    )
    (net (code "80") (name "unconnected-(IC2A-USB_DP-Pad26)") (class "Default")
      (node (ref "IC2") (pin "26") (pinfunction "USB_DP_26") (pintype "bidirectional"))
    )
    (net (code "81") (name "unconnected-(Q1-2-Pad+)") (class "Default")
      (node (ref "Q1") (pin "+") (pinfunction "2_+") (pintype "passive"))
    )
    (net (code "82") (name "unconnected-(U2-(PCINT0{slash}CLKO{slash}ICP1)_PB0-Pad12)") (class "Default")
      (node (ref "U2") (pin "12") (pinfunction "(PCINT0/CLKO/ICP1)_PB0_12") (pintype "bidirectional"))
    )
    (net (code "83") (name "unconnected-(U2-(PCINT1{slash}OC1A)_PB1-Pad13)") (class "Default")
      (node (ref "U2") (pin "13") (pinfunction "(PCINT1/OC1A)_PB1_13") (pintype "bidirectional"))
    )
    (net (code "84") (name "unconnected-(U2-(PCINT2{slash}SS{slash}OC1B)_PB2-Pad14)") (class "Default")
      (node (ref "U2") (pin "14") (pinfunction "(PCINT2/SS/OC1B)_PB2_14") (pintype "bidirectional"))
    )
    (net (code "85") (name "unconnected-(U2-(PCINT3{slash}OC2A{slash}MOSI)_PB3-Pad15)") (class "Default")
      (node (ref "U2") (pin "15") (pinfunction "(PCINT3/OC2A/MOSI)_PB3_15") (pintype "bidirectional"))
    )
    (net (code "86") (name "unconnected-(U2-(PCINT4{slash}MISO)_PB4-Pad16)") (class "Default")
      (node (ref "U2") (pin "16") (pinfunction "(PCINT4/MISO)_PB4_16") (pintype "bidirectional"))
    )
    (net (code "87") (name "unconnected-(U2-(PCINT6{slash}XTAL1{slash}TOSC1)_PB6-Pad7)") (class "Default")
      (node (ref "U2") (pin "7") (pinfunction "(PCINT6/XTAL1/TOSC1)_PB6_7") (pintype "bidirectional"))
    )
    (net (code "88") (name "unconnected-(U2-(PCINT7{slash}XTAL2{slash}TOSC2)_PB7-Pad8)") (class "Default")
      (node (ref "U2") (pin "8") (pinfunction "(PCINT7/XTAL2/TOSC2)_PB7_8") (pintype "bidirectional"))
    )
    (net (code "89") (name "unconnected-(U2-ADC6-Pad19)") (class "Default")
      (node (ref "U2") (pin "19") (pinfunction "ADC6_19") (pintype "input"))
    )
    (net (code "90") (name "unconnected-(U2-ADC7-Pad22)") (class "Default")
      (node (ref "U2") (pin "22") (pinfunction "ADC7_22") (pintype "input"))
    )
    (net (code "91") (name "unconnected-(U2-PC1_(ADC1{slash}PCINT9)-Pad24)") (class "Default")
      (node (ref "U2") (pin "24") (pinfunction "PC1_(ADC1/PCINT9)_24") (pintype "bidirectional"))
    )
    (net (code "92") (name "unconnected-(U2-PC2_(ADC2{slash}PCINT10)-Pad25)") (class "Default")
      (node (ref "U2") (pin "25") (pinfunction "PC2_(ADC2/PCINT10)_25") (pintype "bidirectional"))
    )
    (net (code "93") (name "unconnected-(U2-PC3_(ADC3{slash}PCINT11)-Pad26)") (class "Default")
      (node (ref "U2") (pin "26") (pinfunction "PC3_(ADC3/PCINT11)_26") (pintype "bidirectional"))
    )
    (net (code "94") (name "unconnected-(U2-PC4_(ADC4{slash}SDA{slash}PCINT12)-Pad27)") (class "Default")
      (node (ref "U2") (pin "27") (pinfunction "PC4_(ADC4/SDA/PCINT12)_27") (pintype "bidirectional"))
    )
    (net (code "95") (name "unconnected-(U2-PC5_(ADC5{slash}SCL{slash}PCINT13)-Pad28)") (class "Default")
      (node (ref "U2") (pin "28") (pinfunction "PC5_(ADC5/SCL/PCINT13)_28") (pintype "bidirectional"))
    )
    (net (code "96") (name "unconnected-(X1-PadID)") (class "Default")
      (node (ref "X1") (pin "ID") (pinfunction "ID_ID") (pintype "bidirectional"))
    )
    (net (code "97") (name "unconnected-(X2-5-PadC6)") (class "Default")
      (node (ref "X2") (pin "C6") (pinfunction "5_C6") (pintype "passive"))
    )
  )
)
